# LCMeter3.net
KiCad netlist of a schematic drawn in EAGLE
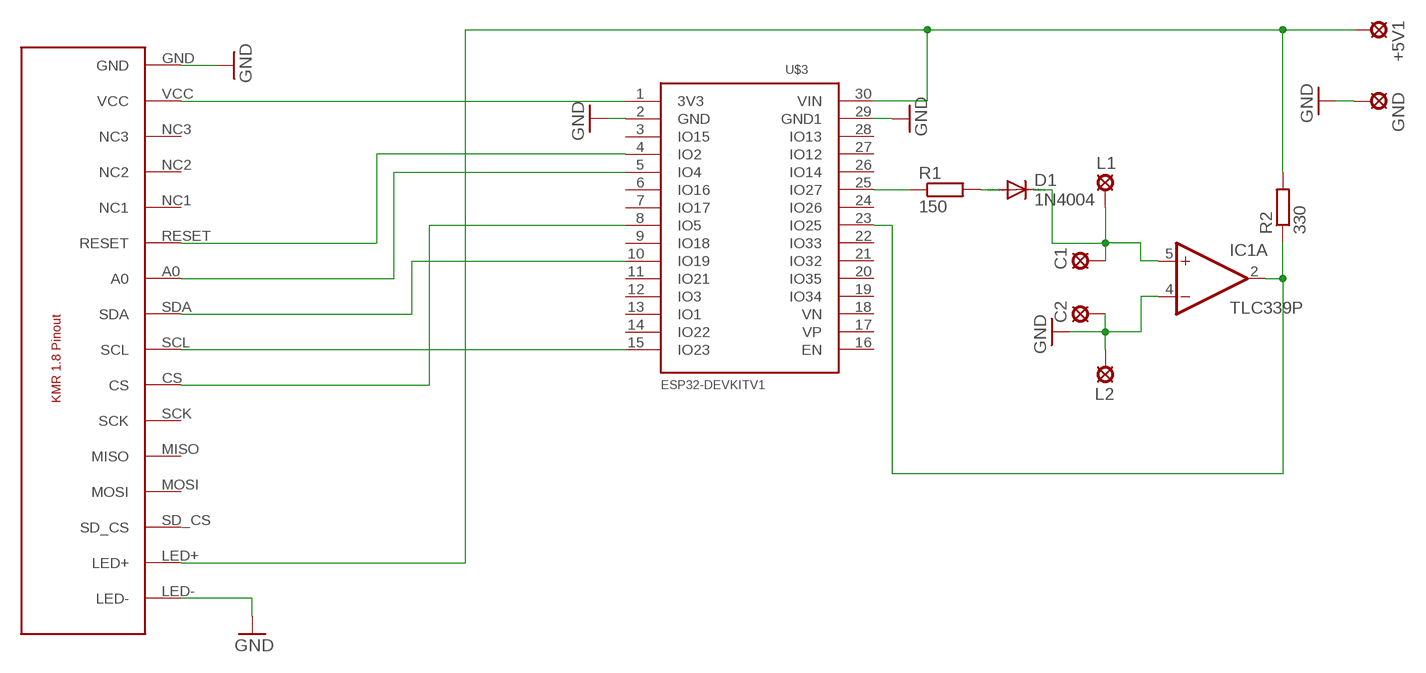
[diagram p0: schematic, sheet 1]

(export (version "E")
  (design (tool "Eeschema 10.0.6"))
  (components
    (comp (ref "+5V1")
      (value "LSP10")
      (footprint "eagle-import:LSP10")
      (libsource (lib "eagle-import") (part "LSP10"))
    )
    (comp (ref "C1")
      (value "LSP10")
      (footprint "eagle-import:LSP10")
      (libsource (lib "eagle-import") (part "LSP10"))
    )
    (comp (ref "C2")
      (value "LSP10")
      (footprint "eagle-import:LSP10")
      (libsource (lib "eagle-import") (part "LSP10"))
    )
    (comp (ref "D1")
      (value "1N4004")
      (footprint "eagle-import:DO41-10")
      (libsource (lib "eagle-import") (part "1N4004"))
    )
    (comp (ref "GND")
      (value "LSP10")
      (footprint "eagle-import:LSP10")
      (libsource (lib "eagle-import") (part "LSP10"))
    )
    (comp (ref "IC1")
      (value "TLC339P")
      (footprint "eagle-import:DIL14")
      (libsource (lib "eagle-import") (part "TLC339P"))
    )
    (comp (ref "L1")
      (value "LSP10")
      (footprint "eagle-import:LSP10")
      (libsource (lib "eagle-import") (part "LSP10"))
    )
    (comp (ref "L2")
      (value "LSP10")
      (footprint "eagle-import:LSP10")
      (libsource (lib "eagle-import") (part "LSP10"))
    )
    (comp (ref "R1")
      (value "150")
      (footprint "eagle-import:0207_10")
      (libsource (lib "eagle-import") (part "R-EU_0207/10"))
    )
    (comp (ref "R2")
      (value "330")
      (footprint "eagle-import:0207_10")
      (libsource (lib "eagle-import") (part "R-EU_0207/10"))
    )
    (comp (ref "U$3")
      (value "ESP32DEVKITV1")
      (footprint "eagle-import:ESP32-DEVKITV1")
      (libsource (lib "eagle-import") (part "ESP32DEVKITV1"))
    )
    (comp (ref "U$4")
      (value "KMR-1.8")
      (footprint "eagle-import:KMR-1.8")
      (libsource (lib "eagle-import") (part "KMR-1.8"))
    )
  )
  (nets
    (net (code "1") (name "GND") (class "Default")
      (node (ref "C2") (pin "MP") (pinfunction "MP_MP") (pintype "passive"))
      (node (ref "GND") (pin "MP") (pinfunction "MP_MP") (pintype "passive"))
      (node (ref "IC1") (pin "4") (pinfunction "-IN_4") (pintype "input"))
      (node (ref "L2") (pin "MP") (pinfunction "MP_MP") (pintype "passive"))
      (node (ref "U$3") (pin "2") (pinfunction "GND_2") (pintype "bidirectional"))
      (node (ref "U$3") (pin "29") (pinfunction "GND1_29") (pintype "bidirectional"))
      (node (ref "U$4") (pin "GND") (pinfunction "GND_GND") (pintype "bidirectional"))
      (node (ref "U$4") (pin "LED-") (pinfunction "LED-_LED-") (pintype "bidirectional"))
    )
    (net (code "2") (name "Net-(D1-PadA)") (class "Default")
      (node (ref "D1") (pin "A") (pinfunction "A_A") (pintype "passive"))
      (node (ref "R1") (pin "2") (pinfunction "2_2") (pintype "passive"))
    )
    (net (code "3") (name "Net-(IC1A-+IN)") (class "Default")
      (node (ref "C1") (pin "MP") (pinfunction "MP_MP") (pintype "passive"))
      (node (ref "D1") (pin "C") (pinfunction "C_C") (pintype "passive"))
      (node (ref "IC1") (pin "5") (pinfunction "+IN_5") (pintype "input"))
      (node (ref "L1") (pin "MP") (pinfunction "MP_MP") (pintype "passive"))
    )
    (net (code "4") (name "Net-(IC1A-OUT)") (class "Default")
      (node (ref "IC1") (pin "2") (pinfunction "OUT_2") (pintype "output"))
      (node (ref "R2") (pin "1") (pinfunction "1_1") (pintype "passive"))
      (node (ref "U$3") (pin "23") (pinfunction "IO25_23") (pintype "bidirectional"))
    )
    (net (code "5") (name "Net-(U$3-3V3)") (class "Default")
      (node (ref "U$3") (pin "1") (pinfunction "3V3_1") (pintype "bidirectional"))
      (node (ref "U$4") (pin "VCC") (pinfunction "VCC_VCC") (pintype "bidirectional"))
    )
    (net (code "6") (name "Net-(U$3-IO2)") (class "Default")
      (node (ref "U$3") (pin "4") (pinfunction "IO2_4") (pintype "bidirectional"))
      (node (ref "U$4") (pin "RESET") (pinfunction "RESET_RESET") (pintype "bidirectional"))
    )
    (net (code "7") (name "Net-(U$3-IO4)") (class "Default")
      (node (ref "U$3") (pin "5") (pinfunction "IO4_5") (pintype "bidirectional"))
      (node (ref "U$4") (pin "A0") (pinfunction "A0_A0") (pintype "bidirectional"))
    )
    (net (code "8") (name "Net-(U$3-IO5)") (class "Default")
      (node (ref "U$3") (pin "8") (pinfunction "IO5_8") (pintype "bidirectional"))
      (node (ref "U$4") (pin "CS") (pinfunction "CS_CS") (pintype "bidirectional"))
    )
    (net (code "9") (name "Net-(U$3-IO19)") (class "Default")
      (node (ref "U$3") (pin "10") (pinfunction "IO19_10") (pintype "bidirectional"))
      (node (ref "U$4") (pin "SDA") (pinfunction "SDA_SDA") (pintype "bidirectional"))
    )
    (net (code "10") (name "Net-(U$3-IO23)") (class "Default")
      (node (ref "U$3") (pin "15") (pinfunction "IO23_15") (pintype "bidirectional"))
      (node (ref "U$4") (pin "SCL") (pinfunction "SCL_SCL") (pintype "bidirectional"))
    )
    (net (code "11") (name "Net-(U$3-IO27)") (class "Default")
      (node (ref "R1") (pin "1") (pinfunction "1_1") (pintype "passive"))
      (node (ref "U$3") (pin "25") (pinfunction "IO27_25") (pintype "bidirectional"))
    )
    (net (code "12") (name "Net-(U$3-VIN)") (class "Default")
      (node (ref "+5V1") (pin "MP") (pinfunction "MP_MP") (pintype "passive"))
      (node (ref "R2") (pin "2") (pinfunction "2_2") (pintype "passive"))
      (node (ref "U$3") (pin "30") (pinfunction "VIN_30") (pintype "bidirectional"))
      (node (ref "U$4") (pin "LED+") (pinfunction "LED+_LED+") (pintype "bidirectional"))
    )
    (net (code "13") (name "unconnected-(U$3-EN-Pad16)") (class "Default")
      (node (ref "U$3") (pin "16") (pinfunction "EN_16") (pintype "bidirectional"))
    )
    (net (code "14") (name "unconnected-(U$3-IO1-Pad13)") (class "Default")
      (node (ref "U$3") (pin "13") (pinfunction "IO1_13") (pintype "bidirectional"))
    )
    (net (code "15") (name "unconnected-(U$3-IO3-Pad12)") (class "Default")
      (node (ref "U$3") (pin "12") (pinfunction "IO3_12") (pintype "bidirectional"))
    )
    (net (code "16") (name "unconnected-(U$3-IO12-Pad27)") (class "Default")
      (node (ref "U$3") (pin "27") (pinfunction "IO12_27") (pintype "bidirectional"))
    )
    (net (code "17") (name "unconnected-(U$3-IO13-Pad28)") (class "Default")
      (node (ref "U$3") (pin "28") (pinfunction "IO13_28") (pintype "bidirectional"))
    )
    (net (code "18") (name "unconnected-(U$3-IO14-Pad26)") (class "Default")
      (node (ref "U$3") (pin "26") (pinfunction "IO14_26") (pintype "bidirectional"))
    )
    (net (code "19") (name "unconnected-(U$3-IO15-Pad3)") (class "Default")
      (node (ref "U$3") (pin "3") (pinfunction "IO15_3") (pintype "bidirectional"))
    )
    (net (code "20") (name "unconnected-(U$3-IO16-Pad6)") (class "Default")
      (node (ref "U$3") (pin "6") (pinfunction "IO16_6") (pintype "bidirectional"))
    )
    (net (code "21") (name "unconnected-(U$3-IO17-Pad7)") (class "Default")
      (node (ref "U$3") (pin "7") (pinfunction "IO17_7") (pintype "bidirectional"))
    )
    (net (code "22") (name "unconnected-(U$3-IO18-Pad9)") (class "Default")
      (node (ref "U$3") (pin "9") (pinfunction "IO18_9") (pintype "bidirectional"))
    )
    (net (code "23") (name "unconnected-(U$3-IO21-Pad11)") (class "Default")
      (node (ref "U$3") (pin "11") (pinfunction "IO21_11") (pintype "bidirectional"))
    )
    (net (code "24") (name "unconnected-(U$3-IO22-Pad14)") (class "Default")
      (node (ref "U$3") (pin "14") (pinfunction "IO22_14") (pintype "bidirectional"))
    )
    (net (code "25") (name "unconnected-(U$3-IO26-Pad24)") (class "Default")
      (node (ref "U$3") (pin "24") (pinfunction "IO26_24") (pintype "bidirectional"))
    )
    (net (code "26") (name "unconnected-(U$3-IO32-Pad21)") (class "Default")
      (node (ref "U$3") (pin "21") (pinfunction "IO32_21") (pintype "bidirectional"))
    )
    (net (code "27") (name "unconnected-(U$3-IO33-Pad22)") (class "Default")
      (node (ref "U$3") (pin "22") (pinfunction "IO33_22") (pintype "bidirectional"))
    )
    (net (code "28") (name "unconnected-(U$3-IO34-Pad19)") (class "Default")
      (node (ref "U$3") (pin "19") (pinfunction "IO34_19") (pintype "bidirectional"))
    )
    (net (code "29") (name "unconnected-(U$3-IO35-Pad20)") (class "Default")
      (node (ref "U$3") (pin "20") (pinfunction "IO35_20") (pintype "bidirectional"))
    )
    (net (code "30") (name "unconnected-(U$3-VN-Pad18)") (class "Default")
      (node (ref "U$3") (pin "18") (pinfunction "VN_18") (pintype "bidirectional"))
    )
    (net (code "31") (name "unconnected-(U$3-VP-Pad17)") (class "Default")
      (node (ref "U$3") (pin "17") (pinfunction "VP_17") (pintype "bidirectional"))
    )
    (net (code "32") (name "unconnected-(U$4-PadMISO)") (class "Default")
      (node (ref "U$4") (pin "MISO") (pinfunction "MISO_MISO") (pintype "bidirectional"))
    )
    (net (code "33") (name "unconnected-(U$4-PadMOSI)") (class "Default")
      (node (ref "U$4") (pin "MOSI") (pinfunction "MOSI_MOSI") (pintype "bidirectional"))
    )
    (net (code "34") (name "unconnected-(U$4-PadNC1)") (class "Default")
      (node (ref "U$4") (pin "NC1") (pinfunction "NC1_NC1") (pintype "bidirectional"))
    )
    (net (code "35") (name "unconnected-(U$4-PadNC2)") (class "Default")
      (node (ref "U$4") (pin "NC2") (pinfunction "NC2_NC2") (pintype "bidirectional"))
    )
    (net (code "36") (name "unconnected-(U$4-PadNC3)") (class "Default")
      (node (ref "U$4") (pin "NC3") (pinfunction "NC3_NC3") (pintype "bidirectional"))
    )
    (net (code "37") (name "unconnected-(U$4-PadSCK)") (class "Default")
      (node (ref "U$4") (pin "SCK") (pinfunction "SCK_SCK") (pintype "bidirectional"))
    )
    (net (code "38") (name "unconnected-(U$4-PadSD_CS)") (class "Default")
      (node (ref "U$4") (pin "SD_CS") (pinfunction "SD_CS_SD_CS") (pintype "bidirectional"))
    )
  )
)
